# M220new.net
KiCad netlist of a schematic drawn in EAGLE
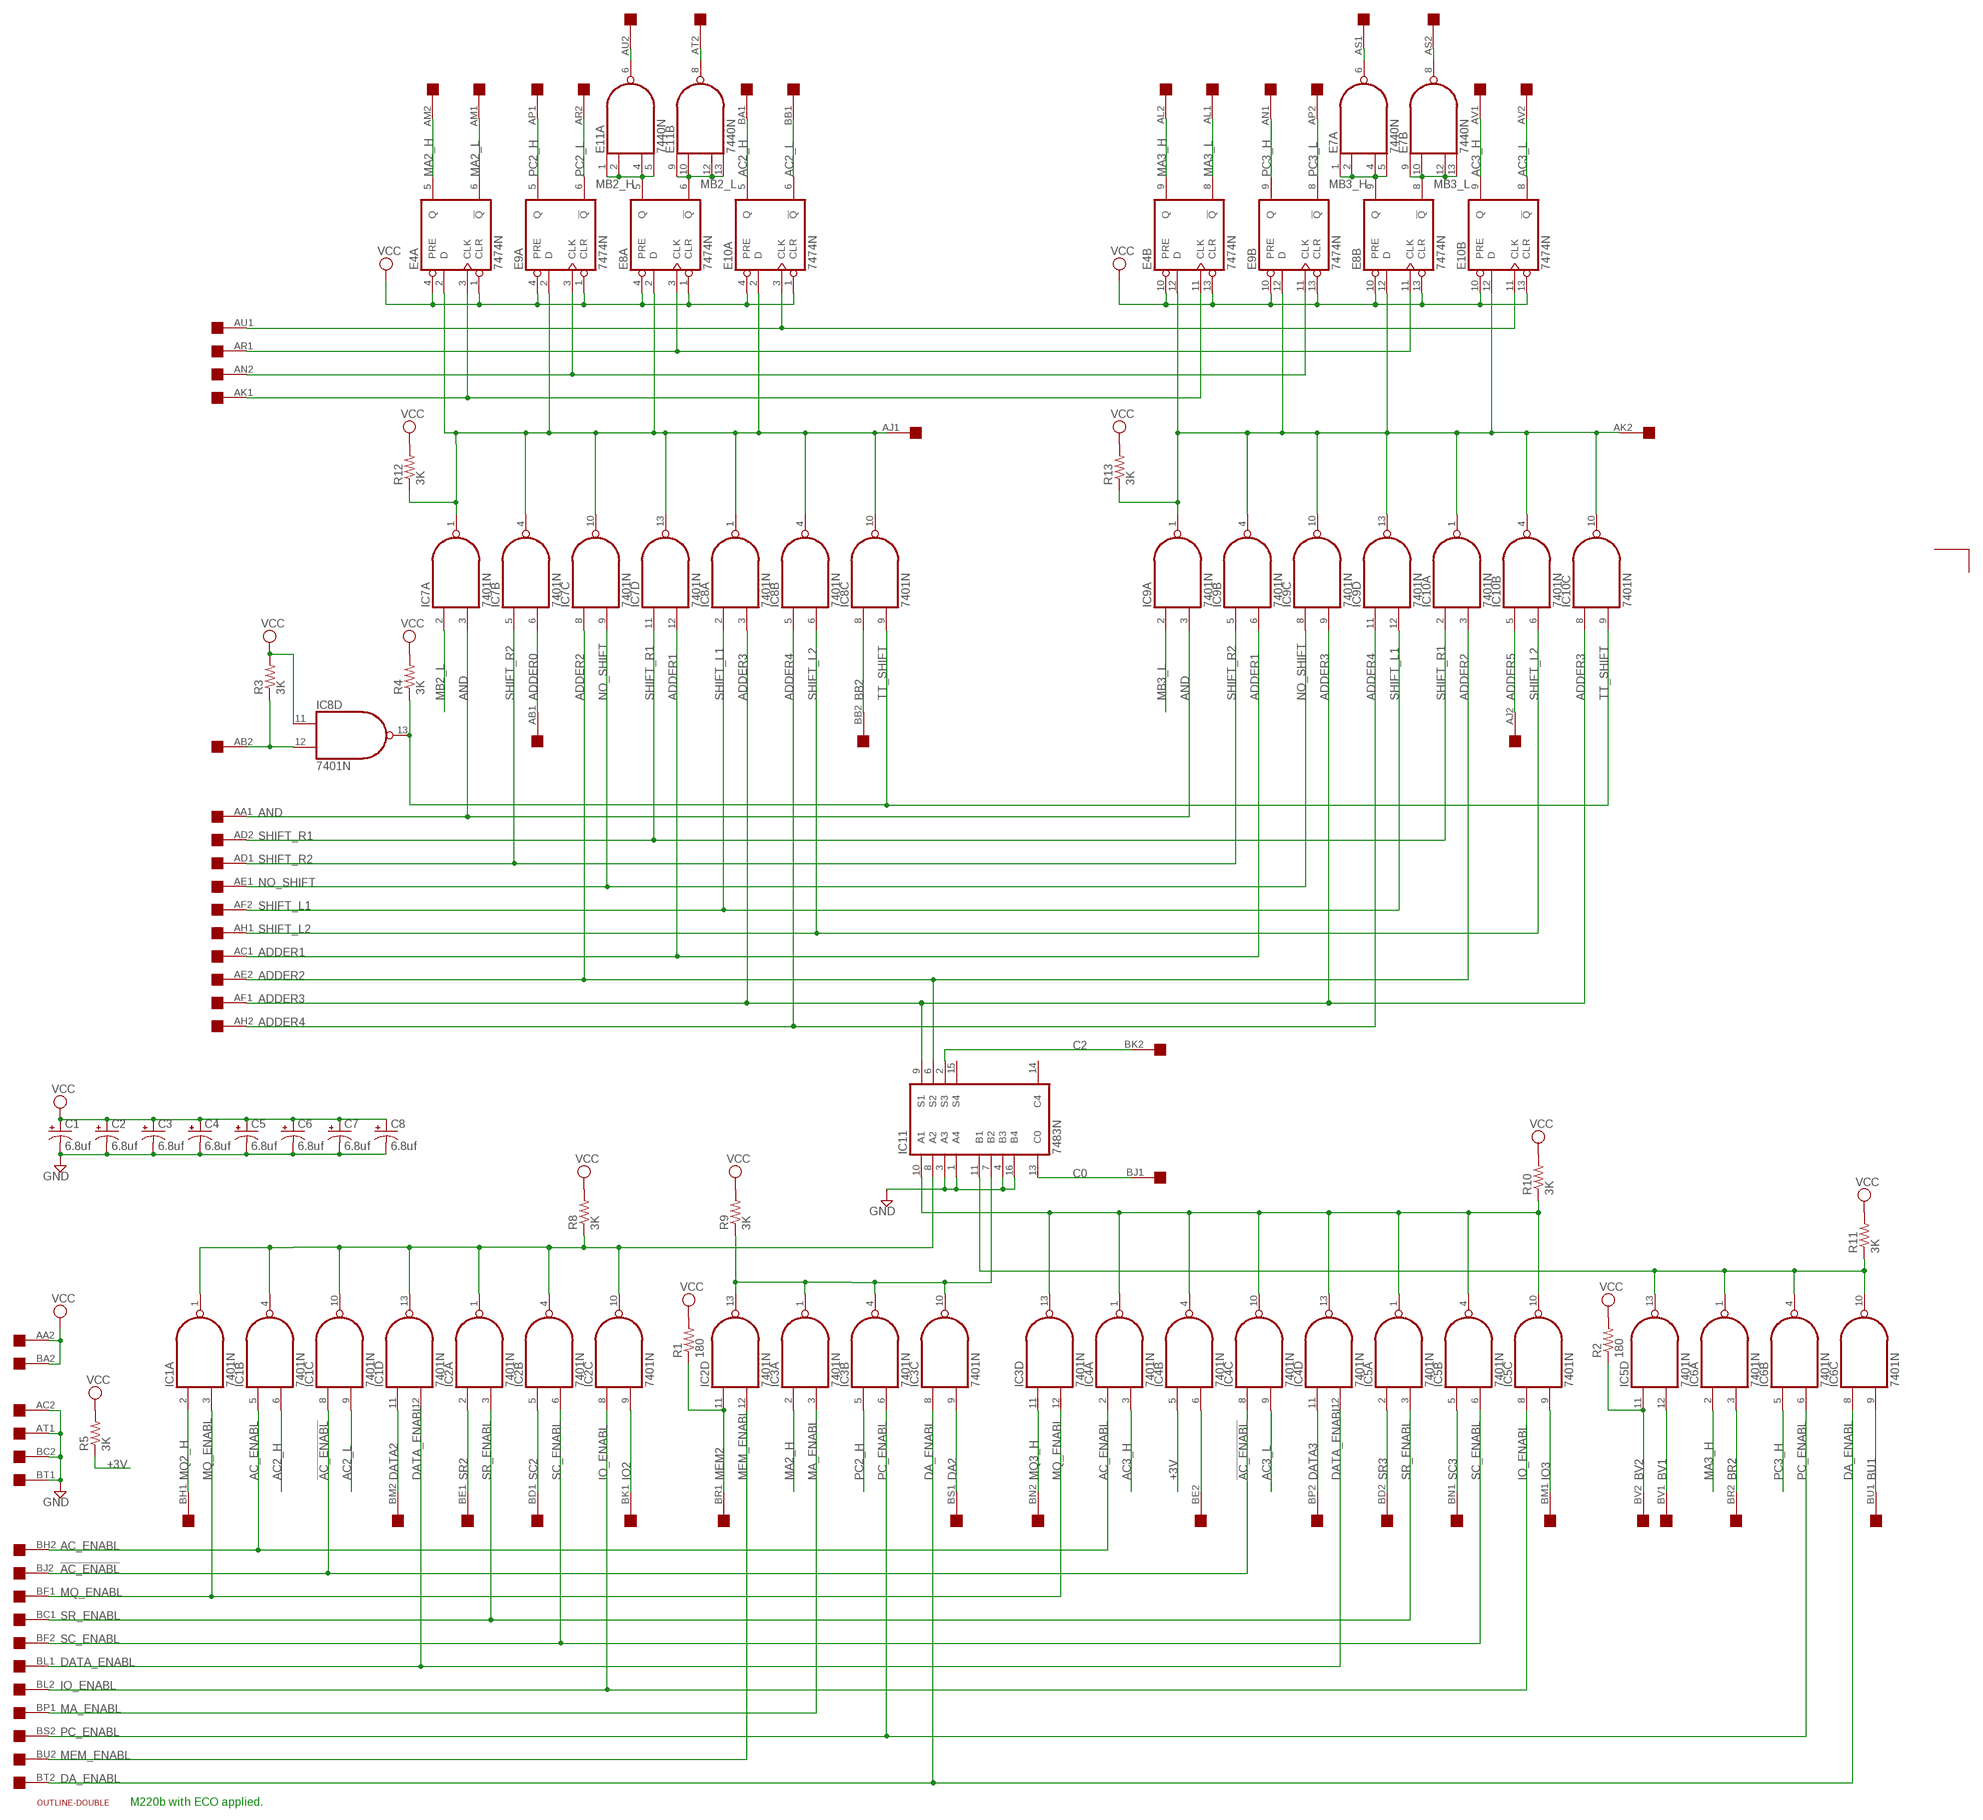
[diagram p0: schematic, sheet 1]

(export (version "E")
  (design (tool "Eeschema 10.0.6"))
  (components
    (comp (ref "C1")
      (value "6.8uf")
      (footprint "eagle-import:E15-5")
      (libsource (lib "eagle-import") (part "CPOL-USE15-5AXIAL"))
    )
    (comp (ref "C2")
      (value "6.8uf")
      (footprint "eagle-import:E15-5")
      (libsource (lib "eagle-import") (part "CPOL-USE15-5AXIAL"))
    )
    (comp (ref "C3")
      (value "6.8uf")
      (footprint "eagle-import:E15-5")
      (libsource (lib "eagle-import") (part "CPOL-USE15-5AXIAL"))
    )
    (comp (ref "C4")
      (value "6.8uf")
      (footprint "eagle-import:E15-5")
      (libsource (lib "eagle-import") (part "CPOL-USE15-5AXIAL"))
    )
    (comp (ref "C5")
      (value "6.8uf")
      (footprint "eagle-import:E15-5")
      (libsource (lib "eagle-import") (part "CPOL-USE15-5AXIAL"))
    )
    (comp (ref "C6")
      (value "6.8uf")
      (footprint "eagle-import:E15-5")
      (libsource (lib "eagle-import") (part "CPOL-USE15-5AXIAL"))
    )
    (comp (ref "C7")
      (value "6.8uf")
      (footprint "eagle-import:E15-5")
      (libsource (lib "eagle-import") (part "CPOL-USE15-5AXIAL"))
    )
    (comp (ref "C8")
      (value "6.8uf")
      (footprint "eagle-import:E15-5")
      (libsource (lib "eagle-import") (part "CPOL-USE15-5AXIAL"))
    )
    (comp (ref "E4")
      (value "7474N")
      (footprint "eagle-import:DIL14")
      (libsource (lib "eagle-import") (part "7474NS"))
    )
    (comp (ref "E7")
      (value "7440N")
      (footprint "eagle-import:DIL14")
      (libsource (lib "eagle-import") (part "7420NS"))
    )
    (comp (ref "E8")
      (value "7474N")
      (footprint "eagle-import:DIL14")
      (libsource (lib "eagle-import") (part "7474NS"))
    )
    (comp (ref "E9")
      (value "7474N")
      (footprint "eagle-import:DIL14")
      (libsource (lib "eagle-import") (part "7474NS"))
    )
    (comp (ref "E10")
      (value "7474N")
      (footprint "eagle-import:DIL14")
      (libsource (lib "eagle-import") (part "7474NS"))
    )
    (comp (ref "E11")
      (value "7440N")
      (footprint "eagle-import:DIL14")
      (libsource (lib "eagle-import") (part "7420NS"))
    )
    (comp (ref "IC1")
      (value "7401N")
      (footprint "eagle-import:DIL14")
      (libsource (lib "eagle-import") (part "7401NLS"))
    )
    (comp (ref "IC2")
      (value "7401N")
      (footprint "eagle-import:DIL14")
      (libsource (lib "eagle-import") (part "7401NLS"))
    )
    (comp (ref "IC3")
      (value "7401N")
      (footprint "eagle-import:DIL14")
      (libsource (lib "eagle-import") (part "7401NLS"))
    )
    (comp (ref "IC4")
      (value "7401N")
      (footprint "eagle-import:DIL14")
      (libsource (lib "eagle-import") (part "7401NLS"))
    )
    (comp (ref "IC5")
      (value "7401N")
      (footprint "eagle-import:DIL14")
      (libsource (lib "eagle-import") (part "7401NLS"))
    )
    (comp (ref "IC6")
      (value "7401N")
      (footprint "eagle-import:DIL14")
      (libsource (lib "eagle-import") (part "7401NLS"))
    )
    (comp (ref "IC7")
      (value "7401N")
      (footprint "eagle-import:DIL14")
      (libsource (lib "eagle-import") (part "7401NLS"))
    )
    (comp (ref "IC8")
      (value "7401N")
      (footprint "eagle-import:DIL14")
      (libsource (lib "eagle-import") (part "7401NLS"))
    )
    (comp (ref "IC9")
      (value "7401N")
      (footprint "eagle-import:DIL14")
      (libsource (lib "eagle-import") (part "7401NLS"))
    )
    (comp (ref "IC10")
      (value "7401N")
      (footprint "eagle-import:DIL14")
      (libsource (lib "eagle-import") (part "7401NLS"))
    )
    (comp (ref "IC11")
      (value "7483N")
      (footprint "eagle-import:DIL16")
      (libsource (lib "eagle-import") (part "7483N"))
    )
    (comp (ref "R1")
      (value "180")
      (footprint "eagle-import:0207_10")
      (libsource (lib "eagle-import") (part "R-US_0207/10"))
    )
    (comp (ref "R2")
      (value "180")
      (footprint "eagle-import:0207_10")
      (libsource (lib "eagle-import") (part "R-US_0207/10"))
    )
    (comp (ref "R3")
      (value "3K")
      (footprint "eagle-import:0207_10")
      (libsource (lib "eagle-import") (part "R-US_0207/10"))
    )
    (comp (ref "R4")
      (value "3K")
      (footprint "eagle-import:0207_10")
      (libsource (lib "eagle-import") (part "R-US_0207/10"))
    )
    (comp (ref "R5")
      (value "3K")
      (footprint "eagle-import:0207_10")
      (libsource (lib "eagle-import") (part "R-US_0207/10"))
    )
    (comp (ref "R8")
      (value "3K")
      (footprint "eagle-import:0207_10")
      (libsource (lib "eagle-import") (part "R-US_0207/10"))
    )
    (comp (ref "R9")
      (value "3K")
      (footprint "eagle-import:0207_10")
      (libsource (lib "eagle-import") (part "R-US_0207/10"))
    )
    (comp (ref "R10")
      (value "3K")
      (footprint "eagle-import:0207_10")
      (libsource (lib "eagle-import") (part "R-US_0207/10"))
    )
    (comp (ref "R11")
      (value "3K")
      (footprint "eagle-import:0207_10")
      (libsource (lib "eagle-import") (part "R-US_0207/10"))
    )
    (comp (ref "R12")
      (value "3K")
      (footprint "eagle-import:0207_10")
      (libsource (lib "eagle-import") (part "R-US_0207/10"))
    )
    (comp (ref "R13")
      (value "3K")
      (footprint "eagle-import:0207_10")
      (libsource (lib "eagle-import") (part "R-US_0207/10"))
    )
    (comp (ref "U$1")
      (value "DOUBLE")
      (footprint "eagle-import:EDGE-CON4")
      (libsource (lib "eagle-import") (part "DOUBLE"))
    )
    (comp (ref "U$2")
      (value "OUTLINE-DOUBLE")
      (footprint "eagle-import:DOUBLE")
      (libsource (lib "eagle-import") (part "OUTLINE-DOUBLE"))
    )
  )
  (nets
    (net (code "1") (name "/+3V") (class "Default")
      (node (ref "IC4") (pin "5") (pinfunction "I0_5") (pintype "input"))
      (node (ref "R5") (pin "1") (pinfunction "1_1") (pintype "passive"))
    )
    (net (code "2") (name "/AC2_H") (class "Default")
      (node (ref "E10") (pin "5") (pinfunction "Q_5") (pintype "output"))
      (node (ref "IC1") (pin "6") (pinfunction "I1_6") (pintype "input"))
      (node (ref "U$1") (pin "BA1") (pinfunction "1_BA1") (pintype "bidirectional"))
    )
    (net (code "3") (name "/AC2_L") (class "Default")
      (node (ref "E10") (pin "6") (pinfunction "~{Q}_6") (pintype "output"))
      (node (ref "IC1") (pin "9") (pinfunction "I1_9") (pintype "input"))
      (node (ref "U$1") (pin "BB1") (pinfunction "1_BB1") (pintype "bidirectional"))
    )
    (net (code "4") (name "/AC3_H") (class "Default")
      (node (ref "E10") (pin "9") (pinfunction "Q_9") (pintype "output"))
      (node (ref "IC4") (pin "3") (pinfunction "I1_3") (pintype "input"))
      (node (ref "U$1") (pin "AV1") (pinfunction "1_AV1") (pintype "bidirectional"))
    )
    (net (code "5") (name "/AC3_L") (class "Default")
      (node (ref "E10") (pin "8") (pinfunction "~{Q}_8") (pintype "output"))
      (node (ref "IC4") (pin "9") (pinfunction "I1_9") (pintype "input"))
      (node (ref "U$1") (pin "AV2") (pinfunction "1_AV2") (pintype "bidirectional"))
    )
    (net (code "6") (name "/AC_ENABL") (class "Default")
      (node (ref "IC1") (pin "5") (pinfunction "I0_5") (pintype "input"))
      (node (ref "IC4") (pin "2") (pinfunction "I0_2") (pintype "input"))
      (node (ref "U$1") (pin "BH2") (pinfunction "1_BH2") (pintype "bidirectional"))
    )
    (net (code "7") (name "/ADDER0") (class "Default")
      (node (ref "IC7") (pin "6") (pinfunction "I1_6") (pintype "input"))
      (node (ref "U$1") (pin "AB1") (pinfunction "1_AB1") (pintype "bidirectional"))
    )
    (net (code "8") (name "/ADDER1") (class "Default")
      (node (ref "IC7") (pin "12") (pinfunction "I1_12") (pintype "input"))
      (node (ref "IC9") (pin "6") (pinfunction "I1_6") (pintype "input"))
      (node (ref "U$1") (pin "AC1") (pinfunction "1_AC1") (pintype "bidirectional"))
    )
    (net (code "9") (name "/ADDER2") (class "Default")
      (node (ref "IC10") (pin "3") (pinfunction "I1_3") (pintype "input"))
      (node (ref "IC11") (pin "6") (pinfunction "S2_6") (pintype "output"))
      (node (ref "IC7") (pin "8") (pinfunction "I0_8") (pintype "input"))
      (node (ref "U$1") (pin "AE2") (pinfunction "1_AE2") (pintype "bidirectional"))
    )
    (net (code "10") (name "/ADDER3") (class "Default")
      (node (ref "IC10") (pin "8") (pinfunction "I0_8") (pintype "input"))
      (node (ref "IC11") (pin "9") (pinfunction "S1_9") (pintype "output"))
      (node (ref "IC8") (pin "3") (pinfunction "I1_3") (pintype "input"))
      (node (ref "IC9") (pin "9") (pinfunction "I1_9") (pintype "input"))
      (node (ref "U$1") (pin "AF1") (pinfunction "1_AF1") (pintype "bidirectional"))
    )
    (net (code "11") (name "/ADDER4") (class "Default")
      (node (ref "IC8") (pin "5") (pinfunction "I0_5") (pintype "input"))
      (node (ref "IC9") (pin "11") (pinfunction "I0_11") (pintype "input"))
      (node (ref "U$1") (pin "AH2") (pinfunction "1_AH2") (pintype "bidirectional"))
    )
    (net (code "12") (name "/ADDER5") (class "Default")
      (node (ref "IC10") (pin "5") (pinfunction "I0_5") (pintype "input"))
      (node (ref "U$1") (pin "AJ2") (pinfunction "1_AJ2") (pintype "bidirectional"))
    )
    (net (code "13") (name "/AND") (class "Default")
      (node (ref "IC7") (pin "3") (pinfunction "I1_3") (pintype "input"))
      (node (ref "IC9") (pin "3") (pinfunction "I1_3") (pintype "input"))
      (node (ref "U$1") (pin "AA1") (pinfunction "1_AA1") (pintype "bidirectional"))
    )
    (net (code "14") (name "/BB2") (class "Default")
      (node (ref "IC8") (pin "8") (pinfunction "I0_8") (pintype "input"))
      (node (ref "U$1") (pin "BB2") (pinfunction "1_BB2") (pintype "bidirectional"))
    )
    (net (code "15") (name "/BR2") (class "Default")
      (node (ref "IC6") (pin "3") (pinfunction "I1_3") (pintype "input"))
      (node (ref "U$1") (pin "BR2") (pinfunction "1_BR2") (pintype "bidirectional"))
    )
    (net (code "16") (name "/BU1") (class "Default")
      (node (ref "IC6") (pin "9") (pinfunction "I1_9") (pintype "input"))
      (node (ref "U$1") (pin "BU1") (pinfunction "1_BU1") (pintype "bidirectional"))
    )
    (net (code "17") (name "/BV1") (class "Default")
      (node (ref "IC5") (pin "12") (pinfunction "I1_12") (pintype "input"))
      (node (ref "U$1") (pin "BV1") (pinfunction "1_BV1") (pintype "bidirectional"))
    )
    (net (code "18") (name "/BV2") (class "Default")
      (node (ref "IC5") (pin "11") (pinfunction "I0_11") (pintype "input"))
      (node (ref "R2") (pin "1") (pinfunction "1_1") (pintype "passive"))
      (node (ref "U$1") (pin "BV2") (pinfunction "1_BV2") (pintype "bidirectional"))
    )
    (net (code "19") (name "/C0") (class "Default")
      (node (ref "IC11") (pin "13") (pinfunction "C0_13") (pintype "input"))
      (node (ref "U$1") (pin "BJ1") (pinfunction "1_BJ1") (pintype "bidirectional"))
    )
    (net (code "20") (name "/C2") (class "Default")
      (node (ref "IC11") (pin "2") (pinfunction "S3_2") (pintype "output"))
      (node (ref "U$1") (pin "BK2") (pinfunction "1_BK2") (pintype "bidirectional"))
    )
    (net (code "21") (name "/DA2") (class "Default")
      (node (ref "IC3") (pin "9") (pinfunction "I1_9") (pintype "input"))
      (node (ref "U$1") (pin "BS1") (pinfunction "1_BS1") (pintype "bidirectional"))
    )
    (net (code "22") (name "/DATA2") (class "Default")
      (node (ref "IC1") (pin "11") (pinfunction "I0_11") (pintype "input"))
      (node (ref "U$1") (pin "BM2") (pinfunction "1_BM2") (pintype "bidirectional"))
    )
    (net (code "23") (name "/DATA3") (class "Default")
      (node (ref "IC4") (pin "11") (pinfunction "I0_11") (pintype "input"))
      (node (ref "U$1") (pin "BP2") (pinfunction "1_BP2") (pintype "bidirectional"))
    )
    (net (code "24") (name "/DATA_ENABL") (class "Default")
      (node (ref "IC1") (pin "12") (pinfunction "I1_12") (pintype "input"))
      (node (ref "IC4") (pin "12") (pinfunction "I1_12") (pintype "input"))
      (node (ref "U$1") (pin "BL1") (pinfunction "1_BL1") (pintype "bidirectional"))
    )
    (net (code "25") (name "/DA_ENABL") (class "Default")
      (node (ref "IC3") (pin "8") (pinfunction "I0_8") (pintype "input"))
      (node (ref "IC6") (pin "8") (pinfunction "I0_8") (pintype "input"))
      (node (ref "U$1") (pin "BT2") (pinfunction "1_BT2") (pintype "bidirectional"))
    )
    (net (code "26") (name "/IO2") (class "Default")
      (node (ref "IC2") (pin "9") (pinfunction "I1_9") (pintype "input"))
      (node (ref "U$1") (pin "BK1") (pinfunction "1_BK1") (pintype "bidirectional"))
    )
    (net (code "27") (name "/IO3") (class "Default")
      (node (ref "IC5") (pin "9") (pinfunction "I1_9") (pintype "input"))
      (node (ref "U$1") (pin "BM1") (pinfunction "1_BM1") (pintype "bidirectional"))
    )
    (net (code "28") (name "/IO_ENABL") (class "Default")
      (node (ref "IC2") (pin "8") (pinfunction "I0_8") (pintype "input"))
      (node (ref "IC5") (pin "8") (pinfunction "I0_8") (pintype "input"))
      (node (ref "U$1") (pin "BL2") (pinfunction "1_BL2") (pintype "bidirectional"))
    )
    (net (code "29") (name "/MA2_H") (class "Default")
      (node (ref "E4") (pin "5") (pinfunction "Q_5") (pintype "output"))
      (node (ref "IC3") (pin "2") (pinfunction "I0_2") (pintype "input"))
      (node (ref "U$1") (pin "AM2") (pinfunction "1_AM2") (pintype "bidirectional"))
    )
    (net (code "30") (name "/MA2_L") (class "Default")
      (node (ref "E4") (pin "6") (pinfunction "~{Q}_6") (pintype "output"))
      (node (ref "U$1") (pin "AM1") (pinfunction "1_AM1") (pintype "bidirectional"))
    )
    (net (code "31") (name "/MA3_H") (class "Default")
      (node (ref "E4") (pin "9") (pinfunction "Q_9") (pintype "output"))
      (node (ref "IC6") (pin "2") (pinfunction "I0_2") (pintype "input"))
      (node (ref "U$1") (pin "AL2") (pinfunction "1_AL2") (pintype "bidirectional"))
    )
    (net (code "32") (name "/MA3_L") (class "Default")
      (node (ref "E4") (pin "8") (pinfunction "~{Q}_8") (pintype "output"))
      (node (ref "U$1") (pin "AL1") (pinfunction "1_AL1") (pintype "bidirectional"))
    )
    (net (code "33") (name "/MA_ENABL") (class "Default")
      (node (ref "IC3") (pin "3") (pinfunction "I1_3") (pintype "input"))
      (node (ref "U$1") (pin "BP1") (pinfunction "1_BP1") (pintype "bidirectional"))
    )
    (net (code "34") (name "/MB2_H") (class "Default")
      (node (ref "E11") (pin "1") (pinfunction "I0_1") (pintype "input"))
      (node (ref "E11") (pin "2") (pinfunction "I1_2") (pintype "input"))
      (node (ref "E11") (pin "4") (pinfunction "I2_4") (pintype "input"))
      (node (ref "E11") (pin "5") (pinfunction "I3_5") (pintype "input"))
      (node (ref "E8") (pin "5") (pinfunction "Q_5") (pintype "output"))
    )
    (net (code "35") (name "/MB2_L") (class "Default")
      (node (ref "E11") (pin "10") (pinfunction "I1_10") (pintype "input"))
      (node (ref "E11") (pin "12") (pinfunction "I2_12") (pintype "input"))
      (node (ref "E11") (pin "13") (pinfunction "I3_13") (pintype "input"))
      (node (ref "E11") (pin "9") (pinfunction "I0_9") (pintype "input"))
      (node (ref "E8") (pin "6") (pinfunction "~{Q}_6") (pintype "output"))
      (node (ref "IC7") (pin "2") (pinfunction "I0_2") (pintype "input"))
    )
    (net (code "36") (name "/MB3_H") (class "Default")
      (node (ref "E7") (pin "1") (pinfunction "I0_1") (pintype "input"))
      (node (ref "E7") (pin "2") (pinfunction "I1_2") (pintype "input"))
      (node (ref "E7") (pin "4") (pinfunction "I2_4") (pintype "input"))
      (node (ref "E7") (pin "5") (pinfunction "I3_5") (pintype "input"))
      (node (ref "E8") (pin "9") (pinfunction "Q_9") (pintype "output"))
    )
    (net (code "37") (name "/MB3_L") (class "Default")
      (node (ref "E7") (pin "10") (pinfunction "I1_10") (pintype "input"))
      (node (ref "E7") (pin "12") (pinfunction "I2_12") (pintype "input"))
      (node (ref "E7") (pin "13") (pinfunction "I3_13") (pintype "input"))
      (node (ref "E7") (pin "9") (pinfunction "I0_9") (pintype "input"))
      (node (ref "E8") (pin "8") (pinfunction "~{Q}_8") (pintype "output"))
      (node (ref "IC9") (pin "2") (pinfunction "I0_2") (pintype "input"))
    )
    (net (code "38") (name "/MEM2") (class "Default")
      (node (ref "IC2") (pin "11") (pinfunction "I0_11") (pintype "input"))
      (node (ref "R1") (pin "1") (pinfunction "1_1") (pintype "passive"))
      (node (ref "U$1") (pin "BR1") (pinfunction "1_BR1") (pintype "bidirectional"))
    )
    (net (code "39") (name "/MEM_ENABL") (class "Default")
      (node (ref "IC2") (pin "12") (pinfunction "I1_12") (pintype "input"))
      (node (ref "U$1") (pin "BU2") (pinfunction "1_BU2") (pintype "bidirectional"))
    )
    (net (code "40") (name "/MQ2_H") (class "Default")
      (node (ref "IC1") (pin "2") (pinfunction "I0_2") (pintype "input"))
      (node (ref "U$1") (pin "BH1") (pinfunction "1_BH1") (pintype "bidirectional"))
    )
    (net (code "41") (name "/MQ3_H") (class "Default")
      (node (ref "IC3") (pin "11") (pinfunction "I0_11") (pintype "input"))
      (node (ref "U$1") (pin "BN2") (pinfunction "1_BN2") (pintype "bidirectional"))
    )
    (net (code "42") (name "/MQ_ENABL") (class "Default")
      (node (ref "IC1") (pin "3") (pinfunction "I1_3") (pintype "input"))
      (node (ref "IC3") (pin "12") (pinfunction "I1_12") (pintype "input"))
      (node (ref "U$1") (pin "BF1") (pinfunction "1_BF1") (pintype "bidirectional"))
    )
    (net (code "43") (name "/NO_SHIFT") (class "Default")
      (node (ref "IC7") (pin "9") (pinfunction "I1_9") (pintype "input"))
      (node (ref "IC9") (pin "8") (pinfunction "I0_8") (pintype "input"))
      (node (ref "U$1") (pin "AE1") (pinfunction "1_AE1") (pintype "bidirectional"))
    )
    (net (code "44") (name "/PC2_H") (class "Default")
      (node (ref "E9") (pin "5") (pinfunction "Q_5") (pintype "output"))
      (node (ref "IC3") (pin "5") (pinfunction "I0_5") (pintype "input"))
      (node (ref "U$1") (pin "AP1") (pinfunction "1_AP1") (pintype "bidirectional"))
    )
    (net (code "45") (name "/PC2_L") (class "Default")
      (node (ref "E9") (pin "6") (pinfunction "~{Q}_6") (pintype "output"))
      (node (ref "U$1") (pin "AR2") (pinfunction "1_AR2") (pintype "bidirectional"))
    )
    (net (code "46") (name "/PC3_H") (class "Default")
      (node (ref "E9") (pin "9") (pinfunction "Q_9") (pintype "output"))
      (node (ref "IC6") (pin "5") (pinfunction "I0_5") (pintype "input"))
      (node (ref "U$1") (pin "AN1") (pinfunction "1_AN1") (pintype "bidirectional"))
    )
    (net (code "47") (name "/PC3_L") (class "Default")
      (node (ref "E9") (pin "8") (pinfunction "~{Q}_8") (pintype "output"))
      (node (ref "U$1") (pin "AP2") (pinfunction "1_AP2") (pintype "bidirectional"))
    )
    (net (code "48") (name "/PC_ENABL") (class "Default")
      (node (ref "IC3") (pin "6") (pinfunction "I1_6") (pintype "input"))
      (node (ref "IC6") (pin "6") (pinfunction "I1_6") (pintype "input"))
      (node (ref "U$1") (pin "BS2") (pinfunction "1_BS2") (pintype "bidirectional"))
    )
    (net (code "49") (name "/SC2") (class "Default")
      (node (ref "IC2") (pin "5") (pinfunction "I0_5") (pintype "input"))
      (node (ref "U$1") (pin "BD1") (pinfunction "1_BD1") (pintype "bidirectional"))
    )
    (net (code "50") (name "/SC3") (class "Default")
      (node (ref "IC5") (pin "5") (pinfunction "I0_5") (pintype "input"))
      (node (ref "U$1") (pin "BN1") (pinfunction "1_BN1") (pintype "bidirectional"))
    )
    (net (code "51") (name "/SC_ENABL") (class "Default")
      (node (ref "IC2") (pin "6") (pinfunction "I1_6") (pintype "input"))
      (node (ref "IC5") (pin "6") (pinfunction "I1_6") (pintype "input"))
      (node (ref "U$1") (pin "BF2") (pinfunction "1_BF2") (pintype "bidirectional"))
    )
    (net (code "52") (name "/SHIFT_L1") (class "Default")
      (node (ref "IC8") (pin "2") (pinfunction "I0_2") (pintype "input"))
      (node (ref "IC9") (pin "12") (pinfunction "I1_12") (pintype "input"))
      (node (ref "U$1") (pin "AF2") (pinfunction "1_AF2") (pintype "bidirectional"))
    )
    (net (code "53") (name "/SHIFT_L2") (class "Default")
      (node (ref "IC10") (pin "6") (pinfunction "I1_6") (pintype "input"))
      (node (ref "IC8") (pin "6") (pinfunction "I1_6") (pintype "input"))
      (node (ref "U$1") (pin "AH1") (pinfunction "1_AH1") (pintype "bidirectional"))
    )
    (net (code "54") (name "/SHIFT_R1") (class "Default")
      (node (ref "IC10") (pin "2") (pinfunction "I0_2") (pintype "input"))
      (node (ref "IC7") (pin "11") (pinfunction "I0_11") (pintype "input"))
      (node (ref "U$1") (pin "AD2") (pinfunction "1_AD2") (pintype "bidirectional"))
    )
    (net (code "55") (name "/SHIFT_R2") (class "Default")
      (node (ref "IC7") (pin "5") (pinfunction "I0_5") (pintype "input"))
      (node (ref "IC9") (pin "5") (pinfunction "I0_5") (pintype "input"))
      (node (ref "U$1") (pin "AD1") (pinfunction "1_AD1") (pintype "bidirectional"))
    )
    (net (code "56") (name "/SR2") (class "Default")
      (node (ref "IC2") (pin "2") (pinfunction "I0_2") (pintype "input"))
      (node (ref "U$1") (pin "BE1") (pinfunction "1_BE1") (pintype "bidirectional"))
    )
    (net (code "57") (name "/SR3") (class "Default")
      (node (ref "IC5") (pin "2") (pinfunction "I0_2") (pintype "input"))
      (node (ref "U$1") (pin "BD2") (pinfunction "1_BD2") (pintype "bidirectional"))
    )
    (net (code "58") (name "/SR_ENABL") (class "Default")
      (node (ref "IC2") (pin "3") (pinfunction "I1_3") (pintype "input"))
      (node (ref "IC5") (pin "3") (pinfunction "I1_3") (pintype "input"))
      (node (ref "U$1") (pin "BC1") (pinfunction "1_BC1") (pintype "bidirectional"))
    )
    (net (code "59") (name "/TT_SHIFT") (class "Default")
      (node (ref "IC10") (pin "9") (pinfunction "I1_9") (pintype "input"))
      (node (ref "IC8") (pin "13") (pinfunction "O_13") (pintype "open_collector"))
      (node (ref "IC8") (pin "9") (pinfunction "I1_9") (pintype "input"))
      (node (ref "R4") (pin "1") (pinfunction "1_1") (pintype "passive"))
    )
    (net (code "60") (name "/~{AC_ENABL}") (class "Default")
      (node (ref "IC1") (pin "8") (pinfunction "I0_8") (pintype "input"))
      (node (ref "IC4") (pin "8") (pinfunction "I0_8") (pintype "input"))
      (node (ref "U$1") (pin "BJ2") (pinfunction "1_BJ2") (pintype "bidirectional"))
    )
    (net (code "61") (name "GND") (class "Default")
      (node (ref "C1") (pin "-") (pinfunction "-_-") (pintype "passive"))
      (node (ref "C2") (pin "-") (pinfunction "-_-") (pintype "passive"))
      (node (ref "C3") (pin "-") (pinfunction "-_-") (pintype "passive"))
      (node (ref "C4") (pin "-") (pinfunction "-_-") (pintype "passive"))
      (node (ref "C5") (pin "-") (pinfunction "-_-") (pintype "passive"))
      (node (ref "C6") (pin "-") (pinfunction "-_-") (pintype "passive"))
      (node (ref "C7") (pin "-") (pinfunction "-_-") (pintype "passive"))
      (node (ref "C8") (pin "-") (pinfunction "-_-") (pintype "passive"))
      (node (ref "IC11") (pin "1") (pinfunction "A4_1") (pintype "input"))
      (node (ref "IC11") (pin "16") (pinfunction "B4_16") (pintype "input"))
      (node (ref "IC11") (pin "3") (pinfunction "A3_3") (pintype "input"))
      (node (ref "IC11") (pin "4") (pinfunction "B3_4") (pintype "input"))
      (node (ref "U$1") (pin "AC2") (pinfunction "1_AC2") (pintype "bidirectional"))
      (node (ref "U$1") (pin "AT1") (pinfunction "1_AT1") (pintype "bidirectional"))
      (node (ref "U$1") (pin "BC2") (pinfunction "1_BC2") (pintype "bidirectional"))
      (node (ref "U$1") (pin "BT1") (pinfunction "1_BT1") (pintype "bidirectional"))
    )
    (net (code "62") (name "Net-(E4A-CLK)") (class "Default")
      (node (ref "E4") (pin "11") (pinfunction "CLK_11") (pintype "input"))
      (node (ref "E4") (pin "3") (pinfunction "CLK_3") (pintype "input"))
      (node (ref "U$1") (pin "AK1") (pinfunction "1_AK1") (pintype "bidirectional"))
    )
    (net (code "63") (name "Net-(E7A-O)") (class "Default")
      (node (ref "E7") (pin "6") (pinfunction "O_6") (pintype "output"))
      (node (ref "U$1") (pin "AS1") (pinfunction "1_AS1") (pintype "bidirectional"))
    )
    (net (code "64") (name "Net-(E7B-O)") (class "Default")
      (node (ref "E7") (pin "8") (pinfunction "O_8") (pintype "output"))
      (node (ref "U$1") (pin "AS2") (pinfunction "1_AS2") (pintype "bidirectional"))
    )
    (net (code "65") (name "Net-(E8A-CLK)") (class "Default")
      (node (ref "E8") (pin "11") (pinfunction "CLK_11") (pintype "input"))
      (node (ref "E8") (pin "3") (pinfunction "CLK_3") (pintype "input"))
      (node (ref "U$1") (pin "AR1") (pinfunction "1_AR1") (pintype "bidirectional"))
    )
    (net (code "66") (name "Net-(E9A-CLK)") (class "Default")
      (node (ref "E9") (pin "11") (pinfunction "CLK_11") (pintype "input"))
      (node (ref "E9") (pin "3") (pinfunction "CLK_3") (pintype "input"))
      (node (ref "U$1") (pin "AN2") (pinfunction "1_AN2") (pintype "bidirectional"))
    )
    (net (code "67") (name "Net-(E10A-CLK)") (class "Default")
      (node (ref "E10") (pin "11") (pinfunction "CLK_11") (pintype "input"))
      (node (ref "E10") (pin "3") (pinfunction "CLK_3") (pintype "input"))
      (node (ref "U$1") (pin "AU1") (pinfunction "1_AU1") (pintype "bidirectional"))
    )
    (net (code "68") (name "Net-(E10A-D)") (class "Default")
      (node (ref "E10") (pin "2") (pinfunction "D_2") (pintype "input"))
      (node (ref "E4") (pin "2") (pinfunction "D_2") (pintype "input"))
      (node (ref "E8") (pin "2") (pinfunction "D_2") (pintype "input"))
      (node (ref "E9") (pin "2") (pinfunction "D_2") (pintype "input"))
      (node (ref "IC7") (pin "1") (pinfunction "O_1") (pintype "open_collector"))
      (node (ref "IC7") (pin "10") (pinfunction "O_10") (pintype "open_collector"))
      (node (ref "IC7") (pin "13") (pinfunction "O_13") (pintype "open_collector"))
      (node (ref "IC7") (pin "4") (pinfunction "O_4") (pintype "open_collector"))
      (node (ref "IC8") (pin "1") (pinfunction "O_1") (pintype "open_collector"))
      (node (ref "IC8") (pin "10") (pinfunction "O_10") (pintype "open_collector"))
      (node (ref "IC8") (pin "4") (pinfunction "O_4") (pintype "open_collector"))
      (node (ref "R12") (pin "1") (pinfunction "1_1") (pintype "passive"))
      (node (ref "U$1") (pin "AJ1") (pinfunction "1_AJ1") (pintype "bidirectional"))
    )
    (net (code "69") (name "Net-(E10B-D)") (class "Default")
      (node (ref "E10") (pin "12") (pinfunction "D_12") (pintype "input"))
      (node (ref "E4") (pin "12") (pinfunction "D_12") (pintype "input"))
      (node (ref "E8") (pin "12") (pinfunction "D_12") (pintype "input"))
      (node (ref "E9") (pin "12") (pinfunction "D_12") (pintype "input"))
      (node (ref "IC10") (pin "1") (pinfunction "O_1") (pintype "open_collector"))
      (node (ref "IC10") (pin "10") (pinfunction "O_10") (pintype "open_collector"))
      (node (ref "IC10") (pin "4") (pinfunction "O_4") (pintype "open_collector"))
      (node (ref "IC9") (pin "1") (pinfunction "O_1") (pintype "open_collector"))
      (node (ref "IC9") (pin "10") (pinfunction "O_10") (pintype "open_collector"))
      (node (ref "IC9") (pin "13") (pinfunction "O_13") (pintype "open_collector"))
      (node (ref "IC9") (pin "4") (pinfunction "O_4") (pintype "open_collector"))
      (node (ref "R13") (pin "1") (pinfunction "1_1") (pintype "passive"))
      (node (ref "U$1") (pin "AK2") (pinfunction "1_AK2") (pintype "bidirectional"))
    )
    (net (code "70") (name "Net-(E11A-O)") (class "Default")
      (node (ref "E11") (pin "6") (pinfunction "O_6") (pintype "output"))
      (node (ref "U$1") (pin "AU2") (pinfunction "1_AU2") (pintype "bidirectional"))
    )
    (net (code "71") (name "Net-(E11B-O)") (class "Default")
      (node (ref "E11") (pin "8") (pinfunction "O_8") (pintype "output"))
      (node (ref "U$1") (pin "AT2") (pinfunction "1_AT2") (pintype "bidirectional"))
    )
    (net (code "72") (name "Net-(IC4B-I1)") (class "Default")
      (node (ref "IC4") (pin "6") (pinfunction "I1_6") (pintype "input"))
      (node (ref "U$1") (pin "BE2") (pinfunction "1_BE2") (pintype "bidirectional"))
    )
    (net (code "73") (name "Net-(IC8D-I1)") (class "Default")
      (node (ref "IC8") (pin "12") (pinfunction "I1_12") (pintype "input"))
      (node (ref "R3") (pin "1") (pinfunction "1_1") (pintype "passive"))
      (node (ref "U$1") (pin "AB2") (pinfunction "1_AB2") (pintype "bidirectional"))
    )
    (net (code "74") (name "Net-(IC11A-A1)") (class "Default")
      (node (ref "IC11") (pin "10") (pinfunction "A1_10") (pintype "input"))
      (node (ref "IC3") (pin "13") (pinfunction "O_13") (pintype "open_collector"))
      (node (ref "IC4") (pin "1") (pinfunction "O_1") (pintype "open_collector"))
      (node (ref "IC4") (pin "10") (pinfunction "O_10") (pintype "open_collector"))
      (node (ref "IC4") (pin "13") (pinfunction "O_13") (pintype "open_collector"))
      (node (ref "IC4") (pin "4") (pinfunction "O_4") (pintype "open_collector"))
      (node (ref "IC5") (pin "1") (pinfunction "O_1") (pintype "open_collector"))
      (node (ref "IC5") (pin "10") (pinfunction "O_10") (pintype "open_collector"))
      (node (ref "IC5") (pin "4") (pinfunction "O_4") (pintype "open_collector"))
      (node (ref "R10") (pin "1") (pinfunction "1_1") (pintype "passive"))
    )
    (net (code "75") (name "Net-(IC11A-A2)") (class "Default")
      (node (ref "IC1") (pin "1") (pinfunction "O_1") (pintype "open_collector"))
      (node (ref "IC1") (pin "10") (pinfunction "O_10") (pintype "open_collector"))
      (node (ref "IC1") (pin "13") (pinfunction "O_13") (pintype "open_collector"))
      (node (ref "IC1") (pin "4") (pinfunction "O_4") (pintype "open_collector"))
      (node (ref "IC11") (pin "8") (pinfunction "A2_8") (pintype "input"))
      (node (ref "IC2") (pin "1") (pinfunction "O_1") (pintype "open_collector"))
      (node (ref "IC2") (pin "10") (pinfunction "O_10") (pintype "open_collector"))
      (node (ref "IC2") (pin "4") (pinfunction "O_4") (pintype "open_collector"))
      (node (ref "R8") (pin "1") (pinfunction "1_1") (pintype "passive"))
    )
    (net (code "76") (name "Net-(IC11A-B1)") (class "Default")
      (node (ref "IC11") (pin "11") (pinfunction "B1_11") (pintype "input"))
      (node (ref "IC5") (pin "13") (pinfunction "O_13") (pintype "open_collector"))
      (node (ref "IC6") (pin "1") (pinfunction "O_1") (pintype "open_collector"))
      (node (ref "IC6") (pin "10") (pinfunction "O_10") (pintype "open_collector"))
      (node (ref "IC6") (pin "4") (pinfunction "O_4") (pintype "open_collector"))
      (node (ref "R11") (pin "1") (pinfunction "1_1") (pintype "passive"))
    )
    (net (code "77") (name "Net-(IC11A-B2)") (class "Default")
      (node (ref "IC11") (pin "7") (pinfunction "B2_7") (pintype "input"))
      (node (ref "IC2") (pin "13") (pinfunction "O_13") (pintype "open_collector"))
      (node (ref "IC3") (pin "1") (pinfunction "O_1") (pintype "open_collector"))
      (node (ref "IC3") (pin "10") (pinfunction "O_10") (pintype "open_collector"))
      (node (ref "IC3") (pin "4") (pinfunction "O_4") (pintype "open_collector"))
      (node (ref "R9") (pin "1") (pinfunction "1_1") (pintype "passive"))
    )
    (net (code "78") (name "VCC") (class "Default")
      (node (ref "C1") (pin "+") (pinfunction "+_+") (pintype "passive"))
      (node (ref "C2") (pin "+") (pinfunction "+_+") (pintype "passive"))
      (node (ref "C3") (pin "+") (pinfunction "+_+") (pintype "passive"))
      (node (ref "C4") (pin "+") (pinfunction "+_+") (pintype "passive"))
      (node (ref "C5") (pin "+") (pinfunction "+_+") (pintype "passive"))
      (node (ref "C6") (pin "+") (pinfunction "+_+") (pintype "passive"))
      (node (ref "C7") (pin "+") (pinfunction "+_+") (pintype "passive"))
      (node (ref "C8") (pin "+") (pinfunction "+_+") (pintype "passive"))
      (node (ref "E10") (pin "1") (pinfunction "CLR_1") (pintype "input"))
      (node (ref "E10") (pin "10") (pinfunction "PRE_10") (pintype "input"))
      (node (ref "E10") (pin "13") (pinfunction "CLR_13") (pintype "input"))
      (node (ref "E10") (pin "4") (pinfunction "PRE_4") (pintype "input"))
      (node (ref "E4") (pin "1") (pinfunction "CLR_1") (pintype "input"))
      (node (ref "E4") (pin "10") (pinfunction "PRE_10") (pintype "input"))
      (node (ref "E4") (pin "13") (pinfunction "CLR_13") (pintype "input"))
      (node (ref "E4") (pin "4") (pinfunction "PRE_4") (pintype "input"))
      (node (ref "E8") (pin "1") (pinfunction "CLR_1") (pintype "input"))
      (node (ref "E8") (pin "10") (pinfunction "PRE_10") (pintype "input"))
      (node (ref "E8") (pin "13") (pinfunction "CLR_13") (pintype "input"))
      (node (ref "E8") (pin "4") (pinfunction "PRE_4") (pintype "input"))
      (node (ref "E9") (pin "1") (pinfunction "CLR_1") (pintype "input"))
      (node (ref "E9") (pin "10") (pinfunction "PRE_10") (pintype "input"))
      (node (ref "E9") (pin "13") (pinfunction "CLR_13") (pintype "input"))
      (node (ref "E9") (pin "4") (pinfunction "PRE_4") (pintype "input"))
      (node (ref "IC8") (pin "11") (pinfunction "I0_11") (pintype "input"))
      (node (ref "R1") (pin "2") (pinfunction "2_2") (pintype "passive"))
      (node (ref "R10") (pin "2") (pinfunction "2_2") (pintype "passive"))
      (node (ref "R11") (pin "2") (pinfunction "2_2") (pintype "passive"))
      (node (ref "R12") (pin "2") (pinfunction "2_2") (pintype "passive"))
      (node (ref "R13") (pin "2") (pinfunction "2_2") (pintype "passive"))
      (node (ref "R2") (pin "2") (pinfunction "2_2") (pintype "passive"))
      (node (ref "R3") (pin "2") (pinfunction "2_2") (pintype "passive"))
      (node (ref "R4") (pin "2") (pinfunction "2_2") (pintype "passive"))
      (node (ref "R5") (pin "2") (pinfunction "2_2") (pintype "passive"))
      (node (ref "R8") (pin "2") (pinfunction "2_2") (pintype "passive"))
      (node (ref "R9") (pin "2") (pinfunction "2_2") (pintype "passive"))
      (node (ref "U$1") (pin "AA2") (pinfunction "1_AA2") (pintype "bidirectional"))
      (node (ref "U$1") (pin "BA2") (pinfunction "1_BA2") (pintype "bidirectional"))
    )
    (net (code "79") (name "unconnected-(IC11A-C4-Pad14)") (class "Default")
      (node (ref "IC11") (pin "14") (pinfunction "C4_14") (pintype "output"))
    )
    (net (code "80") (name "unconnected-(IC11A-S4-Pad15)") (class "Default")
      (node (ref "IC11") (pin "15") (pinfunction "S4_15") (pintype "output"))
    )
  )
)
